# moodbeam_v5.net
KiCad netlist of a schematic drawn in EAGLE
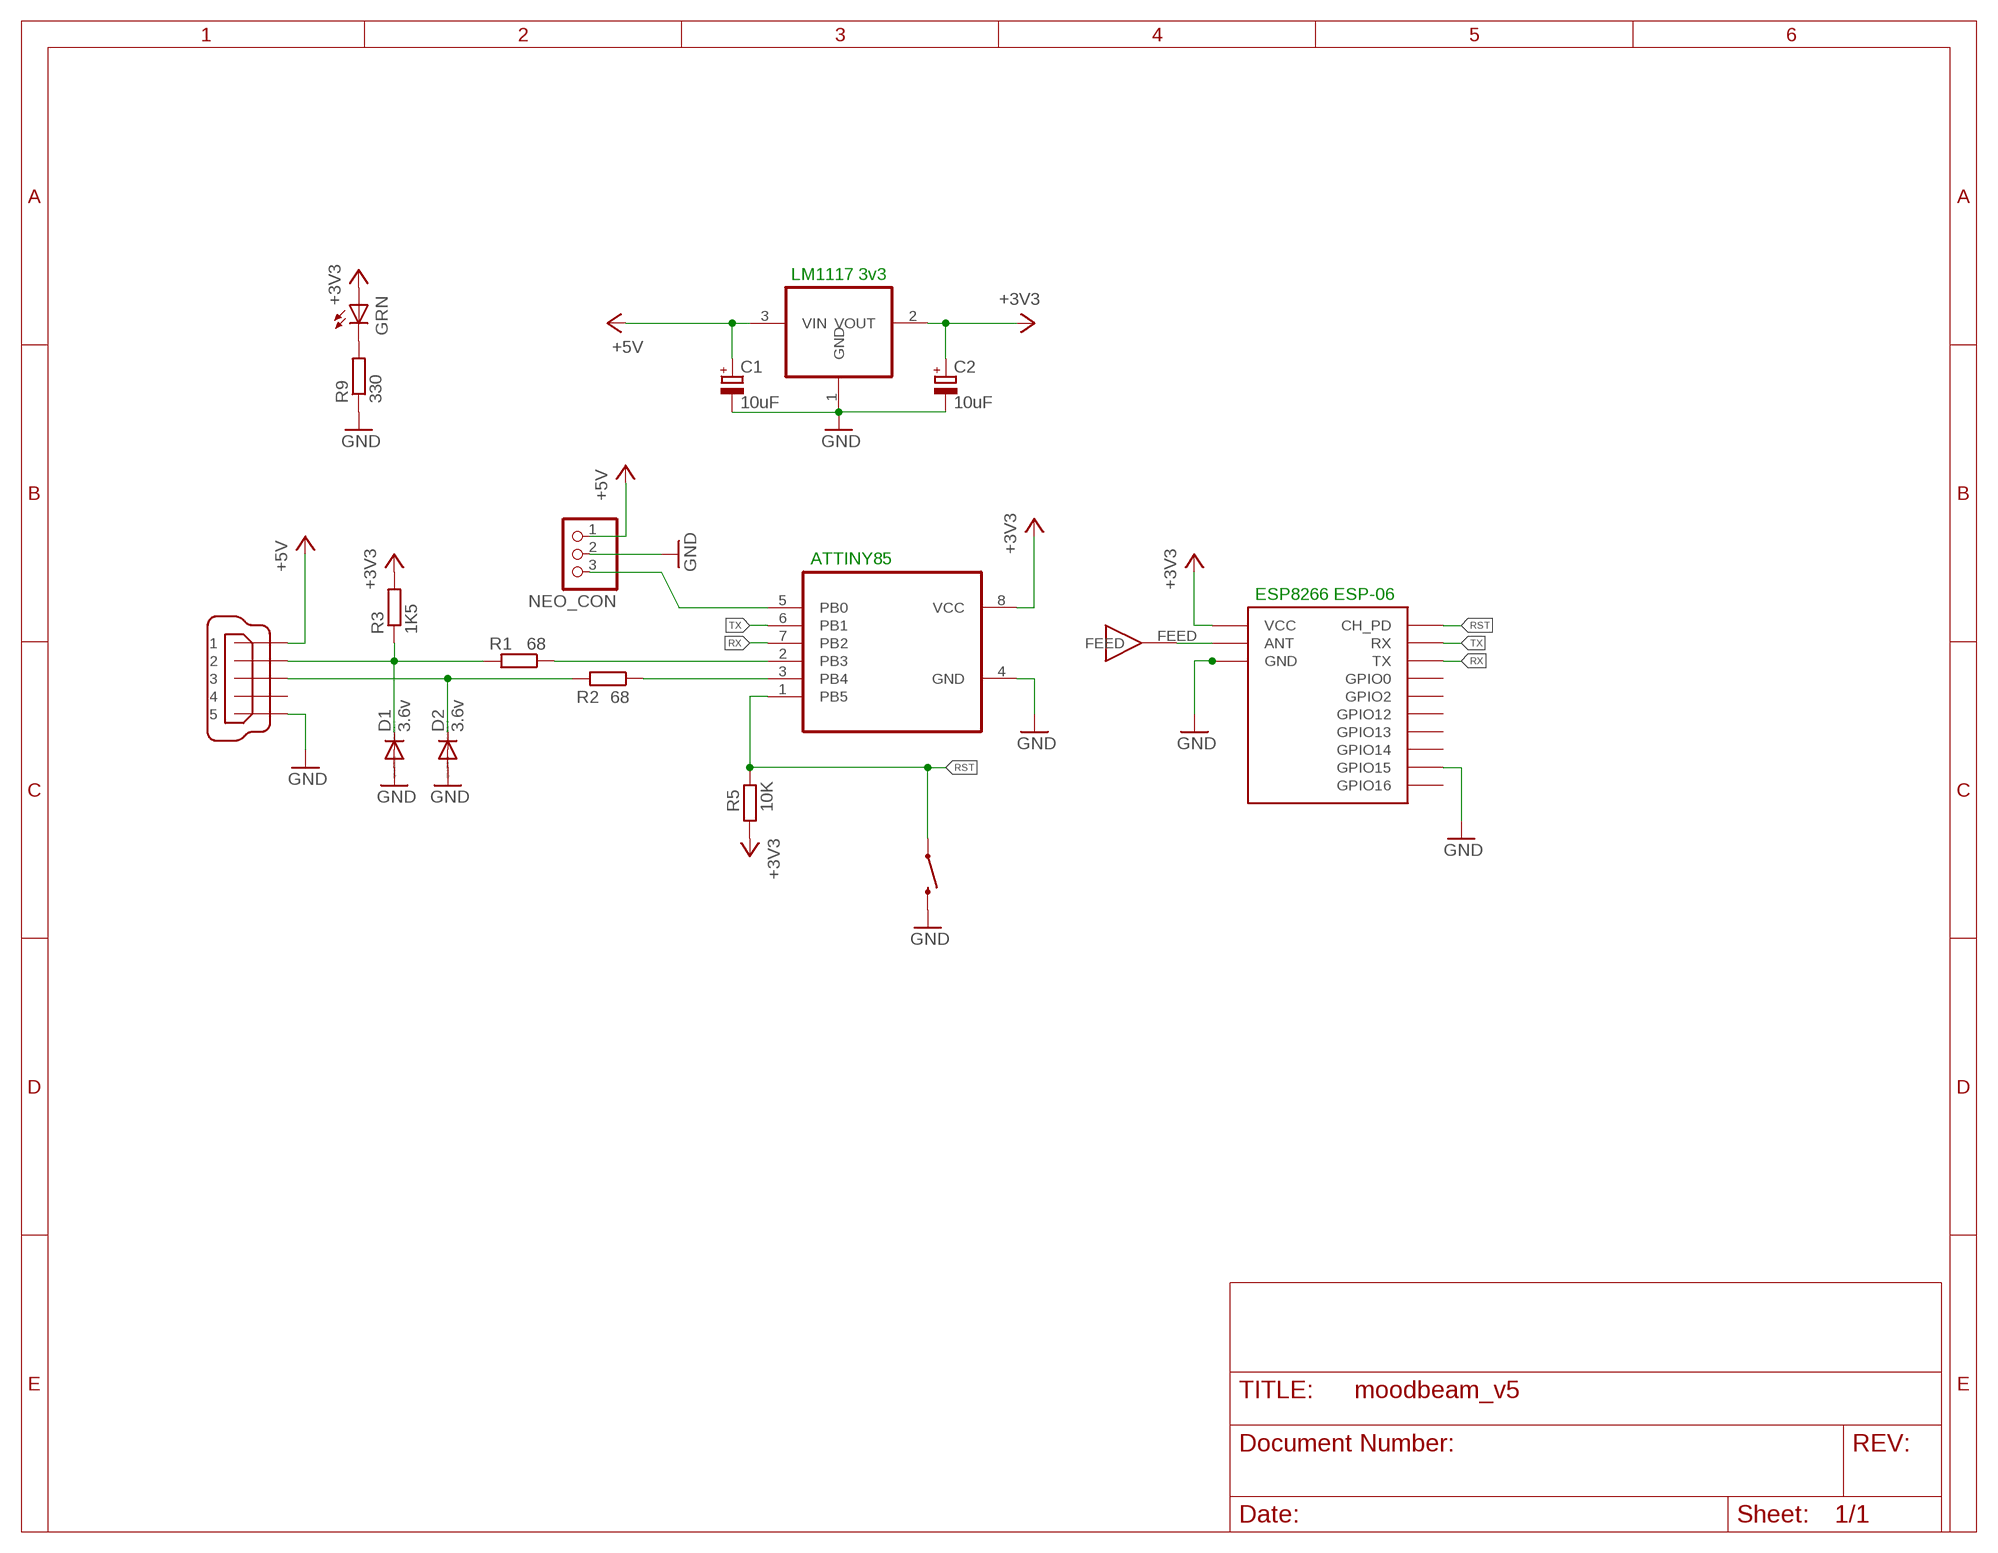
[diagram p0: schematic, sheet 1]

(export (version "E")
  (design (tool "Eeschema 10.0.6"))
  (components
    (comp (ref "C1")
      (value "10uF")
      (footprint "eagle-import:R_2012-12R")
      (libsource (lib "eagle-import") (part "CPOL-EUR/2012-12R"))
    )
    (comp (ref "C2")
      (value "10uF")
      (footprint "eagle-import:R_2012-12R")
      (libsource (lib "eagle-import") (part "CPOL-EUR/2012-12R"))
    )
    (comp (ref "D1")
      (value "3.6v")
      (footprint "eagle-import:DO-214AC")
      (libsource (lib "eagle-import") (part "DIODE-DO-214AC"))
    )
    (comp (ref "D2")
      (value "3.6v")
      (footprint "eagle-import:DO-214AC")
      (libsource (lib "eagle-import") (part "DIODE-DO-214AC"))
    )
    (comp (ref "IC1")
      (value "REG1117")
      (footprint "eagle-import:SOT223")
      (fields (field (name "MPN") "LM1117 3v3"))
      (libsource (lib "eagle-import") (part "REG1117"))
    )
    (comp (ref "JP1")
      (value "NEO_CON")
      (footprint "eagle-import:1X03")
      (libsource (lib "eagle-import") (part "PINHD-1X3"))
    )
    (comp (ref "LED1")
      (value "GRN")
      (footprint "eagle-import:CHIP-LED0805")
      (libsource (lib "eagle-import") (part "LEDCHIP-LED0805"))
    )
    (comp (ref "R1")
      (value "68")
      (footprint "eagle-import:R0805")
      (libsource (lib "eagle-import") (part "R-EU_R0805"))
    )
    (comp (ref "R2")
      (value "68")
      (footprint "eagle-import:R0805")
      (libsource (lib "eagle-import") (part "R-EU_R0805"))
    )
    (comp (ref "R3")
      (value "1K5")
      (footprint "eagle-import:R0805")
      (libsource (lib "eagle-import") (part "R-EU_R0805"))
    )
    (comp (ref "R5")
      (value "10K")
      (footprint "eagle-import:R0805")
      (libsource (lib "eagle-import") (part "R-EU_R0805"))
    )
    (comp (ref "R9")
      (value "330")
      (footprint "eagle-import:R0805")
      (libsource (lib "eagle-import") (part "R-EU_R0805"))
    )
    (comp (ref "S1")
      (value "SWITCH-MOMENTARY-2SMD-1101NE")
      (footprint "eagle-import:TACTILE-SWITCH-1101NE")
      (libsource (lib "eagle-import") (part "SWITCH-MOMENTARY-2SMD-1101NE"))
    )
    (comp (ref "U$1")
      (value "ESP06")
      (footprint "eagle-import:ESP06")
      (libsource (lib "eagle-import") (part "ESP06"))
    )
    (comp (ref "U$2")
      (value "ANT")
      (footprint "eagle-import:ANTENNA-CERAMIC")
      (libsource (lib "eagle-import") (part "ANT"))
    )
    (comp (ref "U1")
      (value "ATTINY85-20SU")
      (footprint "eagle-import:SOIC127P798X216-8N")
      (libsource (lib "eagle-import") (part "ATTINY85-20SU"))
    )
    (comp (ref "X1")
      (value "MINI-USB-32005-201")
      (footprint "eagle-import:32005-201")
      (libsource (lib "eagle-import") (part "MINI-USB-32005-201"))
    )
  )
  (nets
    (net (code "1") (name "+3V3") (class "Default")
      (node (ref "C2") (pin "+") (pinfunction "+_+") (pintype "passive"))
      (node (ref "IC1") (pin "2") (pinfunction "VOUT_2") (pintype "power_in"))
      (node (ref "LED1") (pin "A") (pinfunction "A_A") (pintype "passive"))
      (node (ref "R3") (pin "2") (pinfunction "2_2") (pintype "passive"))
      (node (ref "R5") (pin "1") (pinfunction "1_1") (pintype "passive"))
      (node (ref "U$1") (pin "VCC") (pinfunction "VCC_VCC") (pintype "bidirectional"))
      (node (ref "U1") (pin "8") (pinfunction "VCC_8") (pintype "power_in"))
    )
    (net (code "2") (name "+5V") (class "Default")
      (node (ref "C1") (pin "+") (pinfunction "+_+") (pintype "passive"))
      (node (ref "IC1") (pin "3") (pinfunction "VIN_3") (pintype "input"))
      (node (ref "JP1") (pin "1") (pinfunction "1_1") (pintype "passive"))
      (node (ref "X1") (pin "1") (pinfunction "1_1") (pintype "passive"))
    )
    (net (code "3") (name "GND") (class "Default")
      (node (ref "C1") (pin "-") (pinfunction "-_-") (pintype "passive"))
      (node (ref "C2") (pin "-") (pinfunction "-_-") (pintype "passive"))
      (node (ref "D1") (pin "A") (pinfunction "A_A") (pintype "passive"))
      (node (ref "D2") (pin "A") (pinfunction "A_A") (pintype "passive"))
      (node (ref "IC1") (pin "1") (pinfunction "GND_1") (pintype "power_in"))
      (node (ref "JP1") (pin "2") (pinfunction "2_2") (pintype "passive"))
      (node (ref "R9") (pin "1") (pinfunction "1_1") (pintype "passive"))
      (node (ref "S1") (pin "2") (pinfunction "2_2") (pintype "passive"))
      (node (ref "U$1") (pin "GND") (pinfunction "GND_GND") (pintype "bidirectional"))
      (node (ref "U$1") (pin "GND1") (pinfunction "GND2_GND1") (pintype "bidirectional"))
      (node (ref "U$1") (pin "GND2") (pinfunction "GND3_GND2") (pintype "bidirectional"))
      (node (ref "U$1") (pin "GND3") (pinfunction "GND4_GND3") (pintype "bidirectional"))
      (node (ref "U$1") (pin "GND4") (pinfunction "GND5_GND4") (pintype "bidirectional"))
      (node (ref "U$1") (pin "GND5") (pinfunction "GND6_GND5") (pintype "bidirectional"))
      (node (ref "U$1") (pin "GND6") (pinfunction "GND7_GND6") (pintype "bidirectional"))
      (node (ref "U$1") (pin "GND7") (pinfunction "GND8_GND7") (pintype "bidirectional"))
      (node (ref "U$1") (pin "GPIO15") (pinfunction "GPIO15_GPIO15") (pintype "bidirectional"))
      (node (ref "U1") (pin "4") (pinfunction "GND_4") (pintype "passive"))
      (node (ref "X1") (pin "5") (pinfunction "5_5") (pintype "passive"))
    )
    (net (code "4") (name "Net-(D1-PadC)") (class "Default")
      (node (ref "D1") (pin "C") (pinfunction "C_C") (pintype "passive"))
      (node (ref "R1") (pin "2") (pinfunction "2_2") (pintype "passive"))
      (node (ref "R3") (pin "1") (pinfunction "1_1") (pintype "passive"))
      (node (ref "X1") (pin "2") (pinfunction "2_2") (pintype "passive"))
    )
    (net (code "5") (name "Net-(D2-PadC)") (class "Default")
      (node (ref "D2") (pin "C") (pinfunction "C_C") (pintype "passive"))
      (node (ref "R2") (pin "2") (pinfunction "2_2") (pintype "passive"))
      (node (ref "X1") (pin "3") (pinfunction "3_3") (pintype "passive"))
    )
    (net (code "6") (name "Net-(LED1-PadC)") (class "Default")
      (node (ref "LED1") (pin "C") (pinfunction "C_C") (pintype "passive"))
      (node (ref "R9") (pin "2") (pinfunction "2_2") (pintype "passive"))
    )
    (net (code "7") (name "Net-(U$1-PadANT)") (class "Default")
      (node (ref "U$1") (pin "ANT") (pinfunction "ANT_ANT") (pintype "bidirectional"))
      (node (ref "U$2") (pin "FEED") (pinfunction "FEED_FEED") (pintype "bidirectional"))
    )
    (net (code "8") (name "Net-(U1-PB0)") (class "Default")
      (node (ref "JP1") (pin "3") (pinfunction "3_3") (pintype "passive"))
      (node (ref "U1") (pin "5") (pinfunction "PB0_5") (pintype "bidirectional"))
    )
    (net (code "9") (name "Net-(U1-PB3)") (class "Default")
      (node (ref "R1") (pin "1") (pinfunction "1_1") (pintype "passive"))
      (node (ref "U1") (pin "2") (pinfunction "PB3_2") (pintype "bidirectional"))
    )
    (net (code "10") (name "Net-(U1-PB4)") (class "Default")
      (node (ref "R2") (pin "1") (pinfunction "1_1") (pintype "passive"))
      (node (ref "U1") (pin "3") (pinfunction "PB4_3") (pintype "bidirectional"))
    )
    (net (code "11") (name "RST") (class "Default")
      (node (ref "R5") (pin "2") (pinfunction "2_2") (pintype "passive"))
      (node (ref "S1") (pin "1") (pinfunction "1_1") (pintype "passive"))
      (node (ref "U$1") (pin "CH_PD") (pinfunction "CH_PD_CH_PD") (pintype "bidirectional"))
      (node (ref "U1") (pin "1") (pinfunction "PB5_1") (pintype "bidirectional"))
    )
    (net (code "12") (name "RX") (class "Default")
      (node (ref "U$1") (pin "TX") (pinfunction "TX_TX") (pintype "bidirectional"))
      (node (ref "U1") (pin "7") (pinfunction "PB2_7") (pintype "bidirectional"))
    )
    (net (code "13") (name "TX") (class "Default")
      (node (ref "U$1") (pin "RX") (pinfunction "RX_RX") (pintype "bidirectional"))
      (node (ref "U1") (pin "6") (pinfunction "PB1_6") (pintype "bidirectional"))
    )
    (net (code "14") (name "unconnected-(U$1-PadGPIO0)") (class "Default")
      (node (ref "U$1") (pin "GPIO0") (pinfunction "GPIO0_GPIO0") (pintype "bidirectional"))
    )
    (net (code "15") (name "unconnected-(U$1-PadGPIO2)") (class "Default")
      (node (ref "U$1") (pin "GPIO2") (pinfunction "GPIO2_GPIO2") (pintype "bidirectional"))
    )
    (net (code "16") (name "unconnected-(U$1-PadGPIO12)") (class "Default")
      (node (ref "U$1") (pin "GPIO12") (pinfunction "GPIO12_GPIO12") (pintype "bidirectional"))
    )
    (net (code "17") (name "unconnected-(U$1-PadGPIO13)") (class "Default")
      (node (ref "U$1") (pin "GPIO13") (pinfunction "GPIO13_GPIO13") (pintype "bidirectional"))
    )
    (net (code "18") (name "unconnected-(U$1-PadGPIO14)") (class "Default")
      (node (ref "U$1") (pin "GPIO14") (pinfunction "GPIO14_GPIO14") (pintype "bidirectional"))
    )
    (net (code "19") (name "unconnected-(U$1-PadGPIO16)") (class "Default")
      (node (ref "U$1") (pin "GPIO16") (pinfunction "GPIO16_GPIO16") (pintype "bidirectional"))
    )
    (net (code "20") (name "unconnected-(X1-Pad4)") (class "Default")
      (node (ref "X1") (pin "4") (pinfunction "4_4") (pintype "passive"))
    )
  )
)
